# SCH_kyubo_shared_micro_2024-05-23.net
KiCad netlist of a schematic drawn in EasyEDA
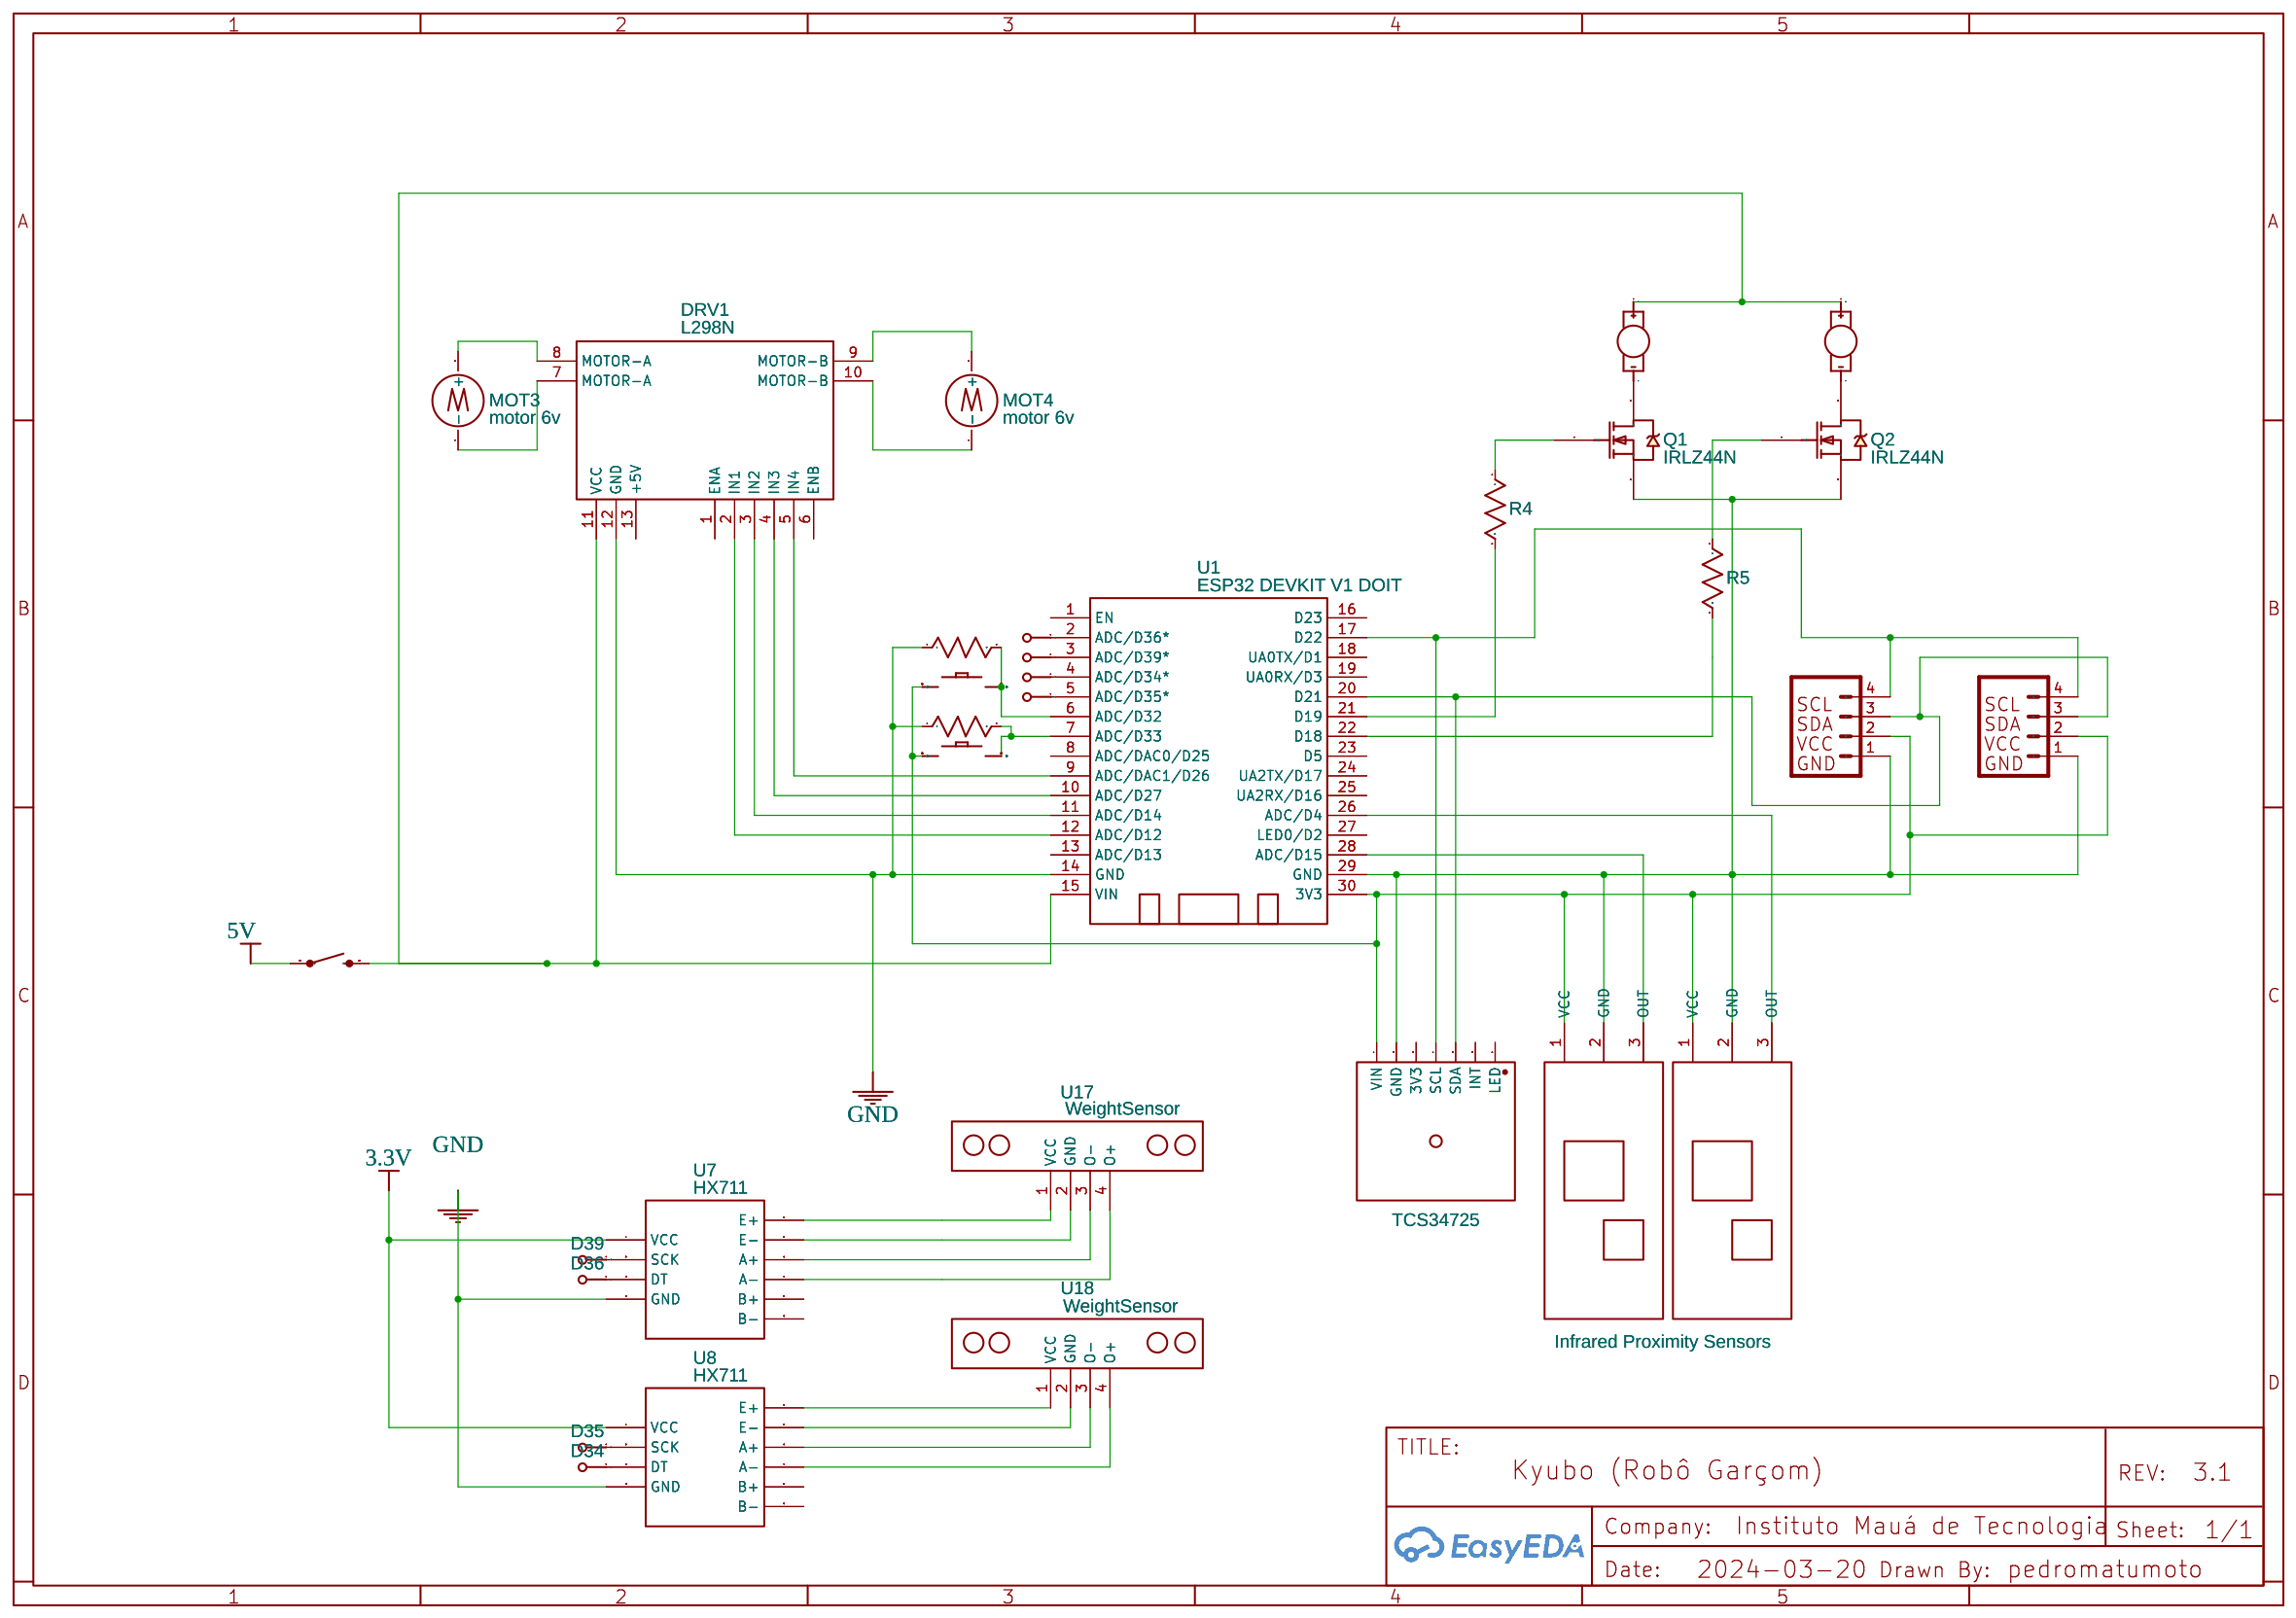
[diagram p0: schematic sheet]

(export (version "E")
  (design (tool "Eeschema 10.0.6"))
  (components
    (comp (ref "1") (value "BUTTON COPY") (libsource (lib "") (part "BUTTON COPY")))
    (comp (ref "2") (value "BUTTON COPY") (libsource (lib "") (part "BUTTON COPY")))
    (comp (ref "DRV1") (value "L298N") (libsource (lib "") (part "L298N")))
    (comp (ref "JP1") (value "I2C_STANDARD_NO_SILK") (libsource (lib "") (part "I2C_STANDARD_NO_SILK")))
    (comp (ref "JP2") (value "I2C_STANDARD_NO_SILK") (libsource (lib "") (part "I2C_STANDARD_NO_SILK")))
    (comp (ref "MOT3")
      (value "motor 6v")
      (fields (field (name "Manufacturer Part") "LCM1027A2445F") (field (name "Manufacturer") "LEADER(立得)"))
      (libsource (lib "") (part "motor 24v"))
    )
    (comp (ref "MOT4")
      (value "motor 6v")
      (fields (field (name "Manufacturer Part") "LCM1027A2445F") (field (name "Manufacturer") "LEADER(立得)"))
      (libsource (lib "") (part "motor 24v"))
    )
    (comp (ref "Q1") (value "IRLZ44N") (libsource (lib "") (part "IRLZ44N")))
    (comp (ref "Q2") (value "IRLZ44N") (libsource (lib "") (part "IRLZ44N")))
    (comp (ref "R1") (value "1k") (libsource (lib "") (part "R_0603_US_1")))
    (comp (ref "R2") (value "1k") (libsource (lib "") (part "R_0603_US_1")))
    (comp (ref "R4") (value "1k") (libsource (lib "") (part "R_0603_US")))
    (comp (ref "R5") (value "1k") (libsource (lib "") (part "R_0603_US")))
    (comp (ref "S1") (value "SWITCH-MOMENTARY") (libsource (lib "") (part "SWITCH-MOMENTARY")))
    (comp (ref "U1") (value "ESP32 DEVKIT V1 DOIT") (libsource (lib "") (part "ESP32 DEVKIT V1 DOIT")))
    (comp (ref "U2") (value "MOTOR10MM") (libsource (lib "") (part "MOTOR10MM")))
    (comp (ref "U3") (value "MOTOR10MM") (libsource (lib "") (part "MOTOR10MM")))
    (comp (ref "U4") (value "TCS34725") (libsource (lib "") (part "TCS34725")))
    (comp (ref "U5")
      (value "Infrared Proximity Sensors")
      (libsource (lib "") (part "Infrared Proximity Sensor"))
    )
    (comp (ref "U6")
      (value "Infrared Proximity Sensor")
      (libsource (lib "") (part "Infrared Proximity Sensor"))
    )
    (comp (ref "U7") (value "HX711") (libsource (lib "") (part "HX711")))
    (comp (ref "U8") (value "HX711") (libsource (lib "") (part "HX711")))
    (comp (ref "U9") (value "OUTPUT2 COPY") (libsource (lib "") (part "OUTPUT2 COPY")))
    (comp (ref "U10") (value "OUTPUT2 COPY") (libsource (lib "") (part "OUTPUT2 COPY")))
    (comp (ref "U11") (value "D39") (libsource (lib "") (part "OUTPUT2 COPY")))
    (comp (ref "U12") (value "D36") (libsource (lib "") (part "OUTPUT2 COPY")))
    (comp (ref "U13") (value "OUTPUT2 COPY") (libsource (lib "") (part "OUTPUT2 COPY")))
    (comp (ref "U14") (value "OUTPUT2 COPY") (libsource (lib "") (part "OUTPUT2 COPY")))
    (comp (ref "U15") (value "D35") (libsource (lib "") (part "OUTPUT2 COPY")))
    (comp (ref "U16") (value "D34") (libsource (lib "") (part "OUTPUT2 COPY")))
    (comp (ref "U17")
      (value "WeightSensor")
      (fields (field (name "Manufacturer Part") "New SchematicLib"))
      (libsource (lib "") (part "WeightSensor"))
    )
    (comp (ref "U18")
      (value "WeightSensor")
      (fields (field (name "Manufacturer Part") "New SchematicLib"))
      (libsource (lib "") (part "WeightSensor"))
    )
  )
  (nets
    (net (code "1") (name "3.3V") (class "Default")
      (node (ref "U7") (pin "7") (pinfunction "VCC_7") (pintype "unspecified"))
      (node (ref "U8") (pin "7") (pinfunction "VCC_7") (pintype "unspecified"))
    )
    (net (code "2") (name "5V") (class "Default")
      (node (ref "S1") (pin "P$1") (pinfunction "1_P$1") (pintype "unspecified"))
    )
    (net (code "3") (name "GND") (class "Default")
      (node (ref "DRV1") (pin "12") (pinfunction "GND_12") (pintype "passive"))
      (node (ref "R1") (pin "1") (pinfunction "1_1") (pintype "unspecified"))
      (node (ref "R2") (pin "1") (pinfunction "1_1") (pintype "unspecified"))
      (node (ref "U1") (pin "14") (pinfunction "GND_14") (pintype "bidirectional"))
      (node (ref "U7") (pin "10") (pinfunction "GND_10") (pintype "unspecified"))
      (node (ref "U8") (pin "10") (pinfunction "GND_10") (pintype "unspecified"))
    )
    (net (code "4") (name "Net-(DRV1-IN1)") (class "Default")
      (node (ref "DRV1") (pin "2") (pinfunction "IN1_2") (pintype "input"))
      (node (ref "U1") (pin "12") (pinfunction "ADC/D12_12") (pintype "bidirectional"))
    )
    (net (code "5") (name "Net-(DRV1-IN2)") (class "Default")
      (node (ref "DRV1") (pin "3") (pinfunction "IN2_3") (pintype "input"))
      (node (ref "U1") (pin "11") (pinfunction "ADC/D14_11") (pintype "bidirectional"))
    )
    (net (code "6") (name "Net-(DRV1-IN3)") (class "Default")
      (node (ref "DRV1") (pin "4") (pinfunction "IN3_4") (pintype "input"))
      (node (ref "U1") (pin "10") (pinfunction "ADC/D27_10") (pintype "bidirectional"))
    )
    (net (code "7") (name "Net-(DRV1-IN4)") (class "Default")
      (node (ref "DRV1") (pin "5") (pinfunction "IN4_5") (pintype "input"))
      (node (ref "U1") (pin "9") (pinfunction "ADC/DAC1/D26_9") (pintype "bidirectional"))
    )
    (net (code "8") (name "Net-(DRV1-VCC)") (class "Default")
      (node (ref "DRV1") (pin "11") (pinfunction "VCC_11") (pintype "passive"))
      (node (ref "S1") (pin "P$2") (pinfunction "2_P$2") (pintype "unspecified"))
      (node (ref "U1") (pin "15") (pinfunction "VIN_15") (pintype "input"))
      (node (ref "U2") (pin "+") (pinfunction "+_+") (pintype "unspecified"))
      (node (ref "U3") (pin "+") (pinfunction "+_+") (pintype "unspecified"))
    )
    (net (code "9") (name "Net-(MOT3-+)") (class "Default")
      (node (ref "DRV1") (pin "8") (pinfunction "MOTOR-A_8") (pintype "output"))
      (node (ref "MOT3") (pin "2") (pinfunction "+_2") (pintype "unspecified"))
    )
    (net (code "10") (name "Net-(MOT3--)") (class "Default")
      (node (ref "DRV1") (pin "7") (pinfunction "MOTOR-A_7") (pintype "output"))
      (node (ref "MOT3") (pin "1") (pinfunction "-_1") (pintype "unspecified"))
    )
    (net (code "11") (name "Net-(MOT4-+)") (class "Default")
      (node (ref "DRV1") (pin "9") (pinfunction "MOTOR-B_9") (pintype "output"))
      (node (ref "MOT4") (pin "2") (pinfunction "+_2") (pintype "unspecified"))
    )
    (net (code "12") (name "Net-(MOT4--)") (class "Default")
      (node (ref "DRV1") (pin "10") (pinfunction "MOTOR-B_10") (pintype "output"))
      (node (ref "MOT4") (pin "1") (pinfunction "-_1") (pintype "unspecified"))
    )
    (net (code "13") (name "Net-(Q1-D)") (class "Default")
      (node (ref "Q1") (pin "2") (pinfunction "D_2") (pintype "unspecified"))
      (node (ref "U2") (pin "-") (pinfunction "-_-") (pintype "unspecified"))
    )
    (net (code "14") (name "Net-(Q1-G)") (class "Default")
      (node (ref "Q1") (pin "1") (pinfunction "G_1") (pintype "unspecified"))
      (node (ref "R4") (pin "1") (pinfunction "1_1") (pintype "unspecified"))
    )
    (net (code "15") (name "Net-(Q1-S)") (class "Default")
      (node (ref "JP1") (pin "1") (pinfunction "1_1") (pintype "unspecified"))
      (node (ref "JP2") (pin "1") (pinfunction "1_1") (pintype "unspecified"))
      (node (ref "Q1") (pin "3") (pinfunction "S_3") (pintype "unspecified"))
      (node (ref "Q2") (pin "3") (pinfunction "S_3") (pintype "unspecified"))
      (node (ref "U1") (pin "29") (pinfunction "GND_29") (pintype "bidirectional"))
      (node (ref "U4") (pin "6") (pinfunction "GND_6") (pintype "unspecified"))
      (node (ref "U5") (pin "2") (pinfunction "GND_2") (pintype "unspecified"))
      (node (ref "U6") (pin "2") (pinfunction "GND_2") (pintype "unspecified"))
    )
    (net (code "16") (name "Net-(Q2-D)") (class "Default")
      (node (ref "Q2") (pin "2") (pinfunction "D_2") (pintype "unspecified"))
      (node (ref "U3") (pin "-") (pinfunction "-_-") (pintype "unspecified"))
    )
    (net (code "17") (name "Net-(Q2-G)") (class "Default")
      (node (ref "Q2") (pin "1") (pinfunction "G_1") (pintype "unspecified"))
      (node (ref "R5") (pin "1") (pinfunction "1_1") (pintype "unspecified"))
    )
    (net (code "18") (name "Net-(U1-3V3)") (class "Default")
      (node (ref "1") (pin "P$GND") (pinfunction "P$GND_P$GND") (pintype "bidirectional"))
      (node (ref "2") (pin "P$GND") (pinfunction "P$GND_P$GND") (pintype "bidirectional"))
      (node (ref "JP1") (pin "2") (pinfunction "2_2") (pintype "unspecified"))
      (node (ref "JP2") (pin "2") (pinfunction "2_2") (pintype "unspecified"))
      (node (ref "U1") (pin "30") (pinfunction "3V3_30") (pintype "bidirectional"))
      (node (ref "U4") (pin "7") (pinfunction "VIN_7") (pintype "unspecified"))
      (node (ref "U5") (pin "1") (pinfunction "VCC_1") (pintype "unspecified"))
      (node (ref "U6") (pin "1") (pinfunction "VCC_1") (pintype "unspecified"))
    )
    (net (code "19") (name "Net-(U1-ADC{slash}D4)") (class "Default")
      (node (ref "U1") (pin "26") (pinfunction "ADC/D4_26") (pintype "bidirectional"))
      (node (ref "U6") (pin "3") (pinfunction "OUT_3") (pintype "unspecified"))
    )
    (net (code "20") (name "Net-(U1-ADC{slash}D15)") (class "Default")
      (node (ref "U1") (pin "28") (pinfunction "ADC/D15_28") (pintype "bidirectional"))
      (node (ref "U5") (pin "3") (pinfunction "OUT_3") (pintype "unspecified"))
    )
    (net (code "21") (name "Net-(U1-ADC{slash}D32)") (class "Default")
      (node (ref "2") (pin "P$ACTIVE") (pinfunction "P$ACTIVE_P$ACTIVE") (pintype "bidirectional"))
      (node (ref "R2") (pin "2") (pinfunction "2_2") (pintype "unspecified"))
      (node (ref "U1") (pin "6") (pinfunction "ADC/D32_6") (pintype "bidirectional"))
    )
    (net (code "22") (name "Net-(U1-ADC{slash}D33)") (class "Default")
      (node (ref "1") (pin "P$ACTIVE") (pinfunction "P$ACTIVE_P$ACTIVE") (pintype "bidirectional"))
      (node (ref "R1") (pin "2") (pinfunction "2_2") (pintype "unspecified"))
      (node (ref "U1") (pin "7") (pinfunction "ADC/D33_7") (pintype "bidirectional"))
    )
    (net (code "23") (name "Net-(U1-ADC{slash}D34*)") (class "Default")
      (node (ref "U1") (pin "4") (pinfunction "ADC/D34*_4") (pintype "input"))
      (node (ref "U13") (pin "1") (pinfunction "1_1") (pintype "output"))
    )
    (net (code "24") (name "Net-(U1-ADC{slash}D35*)") (class "Default")
      (node (ref "U1") (pin "5") (pinfunction "ADC/D35*_5") (pintype "input"))
      (node (ref "U14") (pin "1") (pinfunction "1_1") (pintype "output"))
    )
    (net (code "25") (name "Net-(U1-ADC{slash}D36*)") (class "Default")
      (node (ref "U1") (pin "2") (pinfunction "ADC/D36*_2") (pintype "input"))
      (node (ref "U10") (pin "1") (pinfunction "1_1") (pintype "output"))
    )
    (net (code "26") (name "Net-(U1-ADC{slash}D39*)") (class "Default")
      (node (ref "U1") (pin "3") (pinfunction "ADC/D39*_3") (pintype "input"))
      (node (ref "U9") (pin "1") (pinfunction "1_1") (pintype "output"))
    )
    (net (code "27") (name "Net-(U1-D18)") (class "Default")
      (node (ref "R5") (pin "2") (pinfunction "2_2") (pintype "unspecified"))
      (node (ref "U1") (pin "22") (pinfunction "D18_22") (pintype "bidirectional"))
    )
    (net (code "28") (name "Net-(U1-D19)") (class "Default")
      (node (ref "R4") (pin "2") (pinfunction "2_2") (pintype "unspecified"))
      (node (ref "U1") (pin "21") (pinfunction "D19_21") (pintype "bidirectional"))
    )
    (net (code "29") (name "Net-(U1-D21)") (class "Default")
      (node (ref "JP1") (pin "3") (pinfunction "3_3") (pintype "unspecified"))
      (node (ref "JP2") (pin "3") (pinfunction "3_3") (pintype "unspecified"))
      (node (ref "U1") (pin "20") (pinfunction "D21_20") (pintype "bidirectional"))
      (node (ref "U4") (pin "3") (pinfunction "SDA_3") (pintype "unspecified"))
    )
    (net (code "30") (name "Net-(U1-D22)") (class "Default")
      (node (ref "JP1") (pin "4") (pinfunction "4_4") (pintype "unspecified"))
      (node (ref "JP2") (pin "4") (pinfunction "4_4") (pintype "unspecified"))
      (node (ref "U1") (pin "17") (pinfunction "D22_17") (pintype "bidirectional"))
      (node (ref "U4") (pin "4") (pinfunction "SCL_4") (pintype "unspecified"))
    )
    (net (code "31") (name "Net-(U7-DT)") (class "Default")
      (node (ref "U12") (pin "1") (pinfunction "1_1") (pintype "output"))
      (node (ref "U7") (pin "9") (pinfunction "DT_9") (pintype "unspecified"))
    )
    (net (code "32") (name "Net-(U7-SCK)") (class "Default")
      (node (ref "U11") (pin "1") (pinfunction "1_1") (pintype "output"))
      (node (ref "U7") (pin "8") (pinfunction "SCK_8") (pintype "unspecified"))
    )
    (net (code "33") (name "Net-(U8-DT)") (class "Default")
      (node (ref "U16") (pin "1") (pinfunction "1_1") (pintype "output"))
      (node (ref "U8") (pin "9") (pinfunction "DT_9") (pintype "unspecified"))
    )
    (net (code "34") (name "Net-(U8-SCK)") (class "Default")
      (node (ref "U15") (pin "1") (pinfunction "1_1") (pintype "output"))
      (node (ref "U8") (pin "8") (pinfunction "SCK_8") (pintype "unspecified"))
    )
    (net (code "35") (name "Net-(U17-GND)") (class "Default")
      (node (ref "U17") (pin "2") (pinfunction "GND_2") (pintype "unspecified"))
      (node (ref "U7") (pin "2") (pinfunction "E-_2") (pintype "unspecified"))
    )
    (net (code "36") (name "Net-(U17-O+)") (class "Default")
      (node (ref "U17") (pin "4") (pinfunction "O+_4") (pintype "unspecified"))
      (node (ref "U7") (pin "4") (pinfunction "A-_4") (pintype "unspecified"))
    )
    (net (code "37") (name "Net-(U17-O-)") (class "Default")
      (node (ref "U17") (pin "3") (pinfunction "O-_3") (pintype "unspecified"))
      (node (ref "U7") (pin "3") (pinfunction "A+_3") (pintype "unspecified"))
    )
    (net (code "38") (name "Net-(U17-VCC)") (class "Default")
      (node (ref "U17") (pin "1") (pinfunction "VCC_1") (pintype "unspecified"))
      (node (ref "U7") (pin "1") (pinfunction "E+_1") (pintype "unspecified"))
    )
    (net (code "39") (name "Net-(U18-GND)") (class "Default")
      (node (ref "U18") (pin "2") (pinfunction "GND_2") (pintype "unspecified"))
      (node (ref "U8") (pin "2") (pinfunction "E-_2") (pintype "unspecified"))
    )
    (net (code "40") (name "Net-(U18-O+)") (class "Default")
      (node (ref "U18") (pin "4") (pinfunction "O+_4") (pintype "unspecified"))
      (node (ref "U8") (pin "4") (pinfunction "A-_4") (pintype "unspecified"))
    )
    (net (code "41") (name "Net-(U18-O-)") (class "Default")
      (node (ref "U18") (pin "3") (pinfunction "O-_3") (pintype "unspecified"))
      (node (ref "U8") (pin "3") (pinfunction "A+_3") (pintype "unspecified"))
    )
    (net (code "42") (name "Net-(U18-VCC)") (class "Default")
      (node (ref "U18") (pin "1") (pinfunction "VCC_1") (pintype "unspecified"))
      (node (ref "U8") (pin "1") (pinfunction "E+_1") (pintype "unspecified"))
    )
    (net (code "43") (name "unconnected-(DRV1-+5V-Pad13)") (class "Default")
      (node (ref "DRV1") (pin "13") (pinfunction "+5V_13") (pintype "unspecified"))
    )
    (net (code "44") (name "unconnected-(DRV1-ENA-Pad1)") (class "Default")
      (node (ref "DRV1") (pin "1") (pinfunction "ENA_1") (pintype "input"))
    )
    (net (code "45") (name "unconnected-(DRV1-ENB-Pad6)") (class "Default")
      (node (ref "DRV1") (pin "6") (pinfunction "ENB_6") (pintype "input"))
    )
    (net (code "46") (name "unconnected-(U1-ADC{slash}D13-Pad13)") (class "Default")
      (node (ref "U1") (pin "13") (pinfunction "ADC/D13_13") (pintype "bidirectional"))
    )
    (net (code "47") (name "unconnected-(U1-ADC{slash}DAC0{slash}D25-Pad8)") (class "Default")
      (node (ref "U1") (pin "8") (pinfunction "ADC/DAC0/D25_8") (pintype "bidirectional"))
    )
    (net (code "48") (name "unconnected-(U1-D5-Pad23)") (class "Default")
      (node (ref "U1") (pin "23") (pinfunction "D5_23") (pintype "bidirectional"))
    )
    (net (code "49") (name "unconnected-(U1-D23-Pad16)") (class "Default")
      (node (ref "U1") (pin "16") (pinfunction "D23_16") (pintype "bidirectional"))
    )
    (net (code "50") (name "unconnected-(U1-EN-Pad1)") (class "Default")
      (node (ref "U1") (pin "1") (pinfunction "EN_1") (pintype "bidirectional"))
    )
    (net (code "51") (name "unconnected-(U1-LED0{slash}D2-Pad27)") (class "Default")
      (node (ref "U1") (pin "27") (pinfunction "LED0/D2_27") (pintype "bidirectional"))
    )
    (net (code "52") (name "unconnected-(U1-UA0RX{slash}D3-Pad19)") (class "Default")
      (node (ref "U1") (pin "19") (pinfunction "UA0RX/D3_19") (pintype "bidirectional"))
    )
    (net (code "53") (name "unconnected-(U1-UA0TX{slash}D1-Pad18)") (class "Default")
      (node (ref "U1") (pin "18") (pinfunction "UA0TX/D1_18") (pintype "bidirectional"))
    )
    (net (code "54") (name "unconnected-(U1-UA2RX{slash}D16-Pad25)") (class "Default")
      (node (ref "U1") (pin "25") (pinfunction "UA2RX/D16_25") (pintype "bidirectional"))
    )
    (net (code "55") (name "unconnected-(U1-UA2TX{slash}D17-Pad24)") (class "Default")
      (node (ref "U1") (pin "24") (pinfunction "UA2TX/D17_24") (pintype "bidirectional"))
    )
    (net (code "56") (name "unconnected-(U4-3V3-Pad5)") (class "Default")
      (node (ref "U4") (pin "5") (pinfunction "3V3_5") (pintype "unspecified"))
    )
    (net (code "57") (name "unconnected-(U4-INT-Pad2)") (class "Default")
      (node (ref "U4") (pin "2") (pinfunction "INT_2") (pintype "unspecified"))
    )
    (net (code "58") (name "unconnected-(U4-LED-Pad1)") (class "Default")
      (node (ref "U4") (pin "1") (pinfunction "LED_1") (pintype "unspecified"))
    )
    (net (code "59") (name "unconnected-(U7-B+-Pad5)") (class "Default")
      (node (ref "U7") (pin "5") (pinfunction "B+_5") (pintype "unspecified"))
    )
    (net (code "60") (name "unconnected-(U7-B--Pad6)") (class "Default")
      (node (ref "U7") (pin "6") (pinfunction "B-_6") (pintype "unspecified"))
    )
    (net (code "61") (name "unconnected-(U8-B+-Pad5)") (class "Default")
      (node (ref "U8") (pin "5") (pinfunction "B+_5") (pintype "unspecified"))
    )
    (net (code "62") (name "unconnected-(U8-B--Pad6)") (class "Default")
      (node (ref "U8") (pin "6") (pinfunction "B-_6") (pintype "unspecified"))
    )
  )
)
